# IceBoard-Rev3.net
KiCad netlist of a schematic drawn in EAGLE
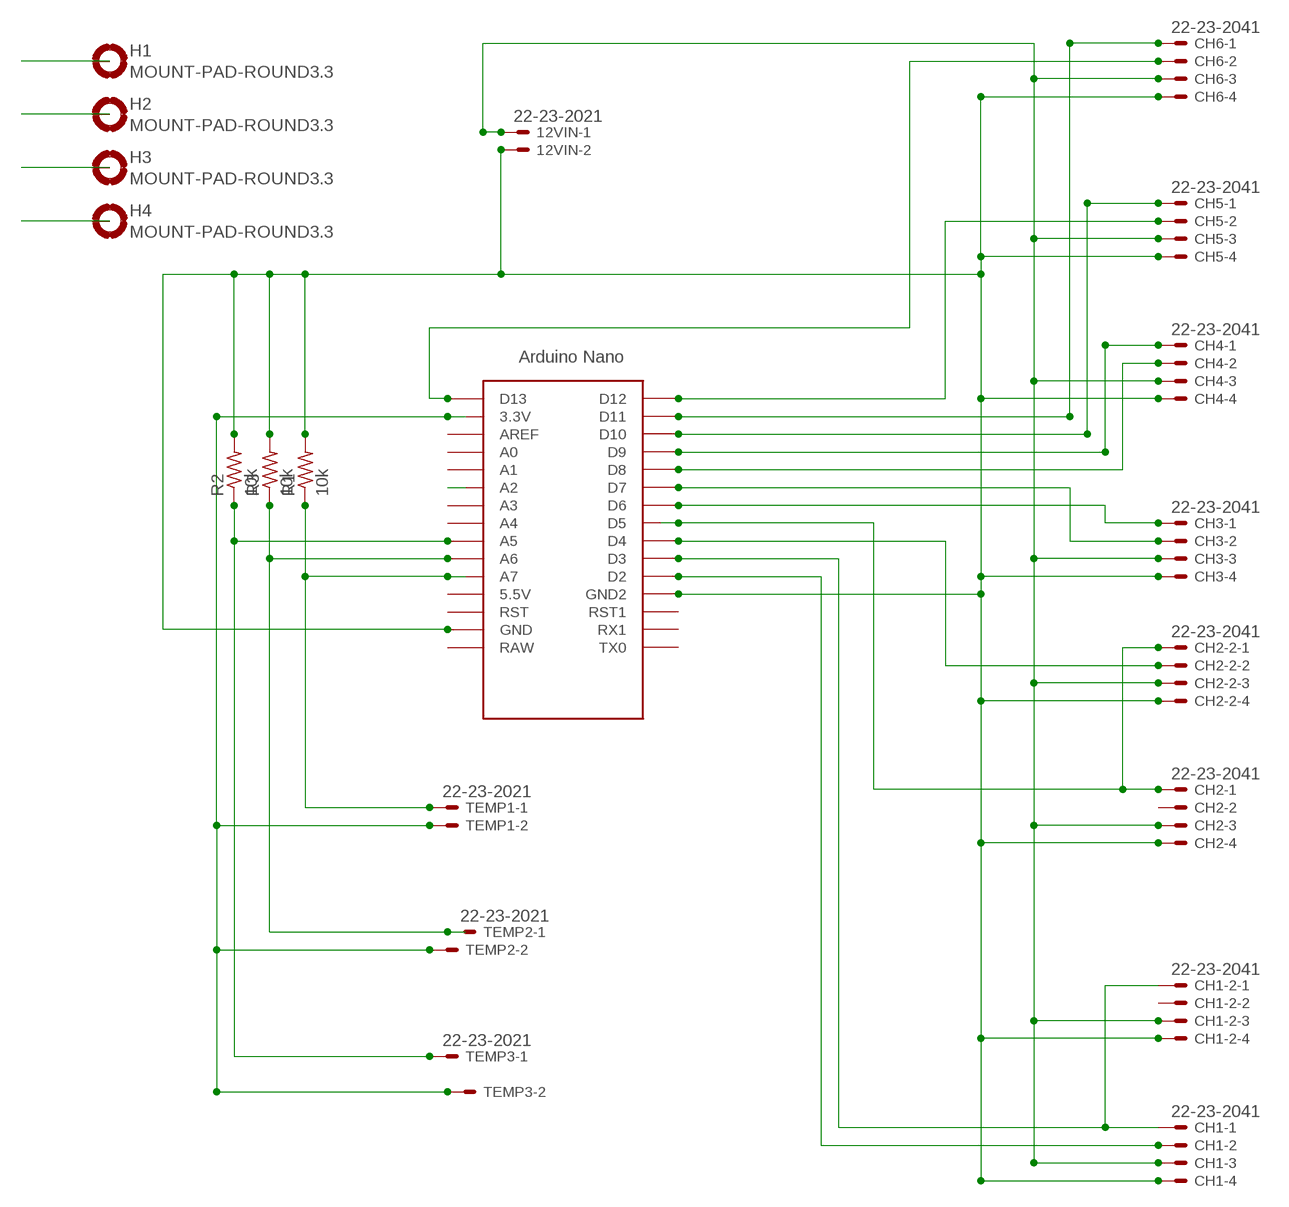
[diagram p0: schematic, sheet 1]

(export (version "E")
  (design (tool "Eeschema 10.0.6"))
  (components
    (comp (ref "12VIN")
      (value "22-23-2021")
      (footprint "eagle-import:22-23-2021")
      (fields (field (name "MF") "MOLEX"))
      (libsource (lib "eagle-import") (part "22-23-2021"))
    )
    (comp (ref "CH1")
      (value "22-23-2041")
      (footprint "eagle-import:22-23-2041")
      (fields (field (name "MF") "MOLEX"))
      (libsource (lib "eagle-import") (part "22-23-2041"))
    )
    (comp (ref "CH1-2")
      (value "22-23-2041")
      (footprint "eagle-import:22-23-2041")
      (fields (field (name "MF") "MOLEX"))
      (libsource (lib "eagle-import") (part "22-23-2041"))
    )
    (comp (ref "CH2")
      (value "22-23-2041")
      (footprint "eagle-import:22-23-2041")
      (fields (field (name "MF") "MOLEX"))
      (libsource (lib "eagle-import") (part "22-23-2041"))
    )
    (comp (ref "CH2-2")
      (value "22-23-2041")
      (footprint "eagle-import:22-23-2041")
      (fields (field (name "MF") "MOLEX"))
      (libsource (lib "eagle-import") (part "22-23-2041"))
    )
    (comp (ref "CH3")
      (value "22-23-2041")
      (footprint "eagle-import:22-23-2041")
      (fields (field (name "MF") "MOLEX"))
      (libsource (lib "eagle-import") (part "22-23-2041"))
    )
    (comp (ref "CH4")
      (value "22-23-2041")
      (footprint "eagle-import:22-23-2041")
      (fields (field (name "MF") "MOLEX"))
      (libsource (lib "eagle-import") (part "22-23-2041"))
    )
    (comp (ref "CH5")
      (value "22-23-2041")
      (footprint "eagle-import:22-23-2041")
      (fields (field (name "MF") "MOLEX"))
      (libsource (lib "eagle-import") (part "22-23-2041"))
    )
    (comp (ref "CH6")
      (value "22-23-2041")
      (footprint "eagle-import:22-23-2041")
      (fields (field (name "MF") "MOLEX"))
      (libsource (lib "eagle-import") (part "22-23-2041"))
    )
    (comp (ref "H1")
      (value "MOUNT-PAD-ROUND3.3")
      (footprint "eagle-import:3,3-PAD")
      (libsource (lib "eagle-import") (part "MOUNT-PAD-ROUND3.3"))
    )
    (comp (ref "H2")
      (value "MOUNT-PAD-ROUND3.3")
      (footprint "eagle-import:3,3-PAD")
      (libsource (lib "eagle-import") (part "MOUNT-PAD-ROUND3.3"))
    )
    (comp (ref "H3")
      (value "MOUNT-PAD-ROUND3.3")
      (footprint "eagle-import:3,3-PAD")
      (libsource (lib "eagle-import") (part "MOUNT-PAD-ROUND3.3"))
    )
    (comp (ref "H4")
      (value "MOUNT-PAD-ROUND3.3")
      (footprint "eagle-import:3,3-PAD")
      (libsource (lib "eagle-import") (part "MOUNT-PAD-ROUND3.3"))
    )
    (comp (ref "R1")
      (value "10k")
      (footprint "eagle-import:R0805")
      (libsource (lib "eagle-import") (part "R-US_R0805"))
    )
    (comp (ref "R2")
      (value "10k")
      (footprint "eagle-import:R0805")
      (libsource (lib "eagle-import") (part "R-US_R0805"))
    )
    (comp (ref "R3")
      (value "10k")
      (footprint "eagle-import:R0805")
      (libsource (lib "eagle-import") (part "R-US_R0805"))
    )
    (comp (ref "TEMP1")
      (value "22-23-2021")
      (footprint "eagle-import:22-23-2021")
      (fields (field (name "MF") "MOLEX"))
      (libsource (lib "eagle-import") (part "22-23-2021"))
    )
    (comp (ref "TEMP2")
      (value "22-23-2021")
      (footprint "eagle-import:22-23-2021")
      (fields (field (name "MF") "MOLEX"))
      (libsource (lib "eagle-import") (part "22-23-2021"))
    )
    (comp (ref "TEMP3")
      (value "22-23-2021")
      (footprint "eagle-import:22-23-2021")
      (fields (field (name "MF") "MOLEX"))
      (libsource (lib "eagle-import") (part "22-23-2021"))
    )
    (comp (ref "U$1")
      (value "NANO")
      (footprint "eagle-import:NANO")
      (libsource (lib "eagle-import") (part "NANO"))
    )
  )
  (nets
    (net (code "1") (name "/GND") (class "Default")
      (node (ref "12VIN") (pin "2") (pinfunction "S_2") (pintype "passive"))
      (node (ref "CH1") (pin "4") (pinfunction "S_4") (pintype "passive"))
      (node (ref "CH1-2") (pin "4") (pinfunction "S_4") (pintype "passive"))
      (node (ref "CH2") (pin "4") (pinfunction "S_4") (pintype "passive"))
      (node (ref "CH2-2") (pin "4") (pinfunction "S_4") (pintype "passive"))
      (node (ref "CH3") (pin "4") (pinfunction "S_4") (pintype "passive"))
      (node (ref "CH4") (pin "4") (pinfunction "S_4") (pintype "passive"))
      (node (ref "CH5") (pin "4") (pinfunction "S_4") (pintype "passive"))
      (node (ref "CH6") (pin "4") (pinfunction "S_4") (pintype "passive"))
      (node (ref "R1") (pin "2") (pinfunction "2_2") (pintype "passive"))
      (node (ref "R2") (pin "2") (pinfunction "2_2") (pintype "passive"))
      (node (ref "R3") (pin "2") (pinfunction "2_2") (pintype "passive"))
      (node (ref "U$1") (pin "GND") (pinfunction "GND_GND") (pintype "bidirectional"))
      (node (ref "U$1") (pin "GND1") (pinfunction "GND2_GND1") (pintype "bidirectional"))
    )
    (net (code "2") (name "Net-(12VINA-S)") (class "Default")
      (node (ref "12VIN") (pin "1") (pinfunction "S_1") (pintype "passive"))
      (node (ref "CH1") (pin "3") (pinfunction "S_3") (pintype "passive"))
      (node (ref "CH1-2") (pin "3") (pinfunction "S_3") (pintype "passive"))
      (node (ref "CH2") (pin "3") (pinfunction "S_3") (pintype "passive"))
      (node (ref "CH2-2") (pin "3") (pinfunction "S_3") (pintype "passive"))
      (node (ref "CH3") (pin "3") (pinfunction "S_3") (pintype "passive"))
      (node (ref "CH4") (pin "3") (pinfunction "S_3") (pintype "passive"))
      (node (ref "CH5") (pin "3") (pinfunction "S_3") (pintype "passive"))
      (node (ref "CH6") (pin "3") (pinfunction "S_3") (pintype "passive"))
    )
    (net (code "3") (name "Net-(CH1-2A-S)") (class "Default")
      (node (ref "CH1") (pin "1") (pinfunction "S_1") (pintype "passive"))
      (node (ref "CH1-2") (pin "1") (pinfunction "S_1") (pintype "passive"))
      (node (ref "U$1") (pin "D3") (pinfunction "D3_D3") (pintype "bidirectional"))
    )
    (net (code "4") (name "Net-(CH1B-S)") (class "Default")
      (node (ref "CH1") (pin "2") (pinfunction "S_2") (pintype "passive"))
      (node (ref "U$1") (pin "D2") (pinfunction "D2_D2") (pintype "bidirectional"))
    )
    (net (code "5") (name "Net-(CH2-2A-S)") (class "Default")
      (node (ref "CH2") (pin "1") (pinfunction "S_1") (pintype "passive"))
      (node (ref "CH2-2") (pin "1") (pinfunction "S_1") (pintype "passive"))
      (node (ref "U$1") (pin "D5") (pinfunction "D5_D5") (pintype "bidirectional"))
    )
    (net (code "6") (name "Net-(CH2-2B-S)") (class "Default")
      (node (ref "CH2-2") (pin "2") (pinfunction "S_2") (pintype "passive"))
      (node (ref "U$1") (pin "D4") (pinfunction "D4_D4") (pintype "bidirectional"))
    )
    (net (code "7") (name "Net-(CH3A-S)") (class "Default")
      (node (ref "CH3") (pin "1") (pinfunction "S_1") (pintype "passive"))
      (node (ref "U$1") (pin "D6") (pinfunction "D6_D6") (pintype "bidirectional"))
    )
    (net (code "8") (name "Net-(CH3B-S)") (class "Default")
      (node (ref "CH3") (pin "2") (pinfunction "S_2") (pintype "passive"))
      (node (ref "U$1") (pin "D7") (pinfunction "D7_D7") (pintype "bidirectional"))
    )
    (net (code "9") (name "Net-(CH4A-S)") (class "Default")
      (node (ref "CH4") (pin "1") (pinfunction "S_1") (pintype "passive"))
      (node (ref "U$1") (pin "D9") (pinfunction "D9_D9") (pintype "bidirectional"))
    )
    (net (code "10") (name "Net-(CH4B-S)") (class "Default")
      (node (ref "CH4") (pin "2") (pinfunction "S_2") (pintype "passive"))
      (node (ref "U$1") (pin "D8") (pinfunction "D8_D8") (pintype "bidirectional"))
    )
    (net (code "11") (name "Net-(CH5A-S)") (class "Default")
      (node (ref "CH5") (pin "1") (pinfunction "S_1") (pintype "passive"))
      (node (ref "U$1") (pin "D10") (pinfunction "D10_D10") (pintype "bidirectional"))
    )
    (net (code "12") (name "Net-(CH5B-S)") (class "Default")
      (node (ref "CH5") (pin "2") (pinfunction "S_2") (pintype "passive"))
      (node (ref "U$1") (pin "D12") (pinfunction "D12_D12") (pintype "bidirectional"))
    )
    (net (code "13") (name "Net-(CH6A-S)") (class "Default")
      (node (ref "CH6") (pin "1") (pinfunction "S_1") (pintype "passive"))
      (node (ref "U$1") (pin "D11") (pinfunction "D11_D11") (pintype "bidirectional"))
    )
    (net (code "14") (name "Net-(CH6B-S)") (class "Default")
      (node (ref "CH6") (pin "2") (pinfunction "S_2") (pintype "passive"))
      (node (ref "U$1") (pin "D13") (pinfunction "D13_D13") (pintype "bidirectional"))
    )
    (net (code "15") (name "Net-(TEMP1A-S)") (class "Default")
      (node (ref "R1") (pin "1") (pinfunction "1_1") (pintype "passive"))
      (node (ref "TEMP1") (pin "1") (pinfunction "S_1") (pintype "passive"))
      (node (ref "U$1") (pin "A7") (pinfunction "A7_A7") (pintype "bidirectional"))
    )
    (net (code "16") (name "Net-(TEMP1B-S)") (class "Default")
      (node (ref "TEMP1") (pin "2") (pinfunction "S_2") (pintype "passive"))
      (node (ref "TEMP2") (pin "2") (pinfunction "S_2") (pintype "passive"))
      (node (ref "TEMP3") (pin "2") (pinfunction "S_2") (pintype "passive"))
      (node (ref "U$1") (pin "3.3V") (pinfunction "3.3V_3.3V") (pintype "bidirectional"))
    )
    (net (code "17") (name "Net-(TEMP2A-S)") (class "Default")
      (node (ref "R3") (pin "1") (pinfunction "1_1") (pintype "passive"))
      (node (ref "TEMP2") (pin "1") (pinfunction "S_1") (pintype "passive"))
      (node (ref "U$1") (pin "A6") (pinfunction "A6_A6") (pintype "bidirectional"))
    )
    (net (code "18") (name "Net-(TEMP3A-S)") (class "Default")
      (node (ref "R2") (pin "1") (pinfunction "1_1") (pintype "passive"))
      (node (ref "TEMP3") (pin "1") (pinfunction "S_1") (pintype "passive"))
      (node (ref "U$1") (pin "A5") (pinfunction "A5_A5") (pintype "bidirectional"))
    )
    (net (code "19") (name "unconnected-(CH1-2B-S-Pad2)") (class "Default")
      (node (ref "CH1-2") (pin "2") (pinfunction "S_2") (pintype "passive"))
    )
    (net (code "20") (name "unconnected-(CH2B-S-Pad2)") (class "Default")
      (node (ref "CH2") (pin "2") (pinfunction "S_2") (pintype "passive"))
    )
    (net (code "21") (name "unconnected-(H1-MOUNT-PadB3,3)") (class "Default")
      (node (ref "H1") (pin "B3,3") (pinfunction "MOUNT_B3,3") (pintype "passive"))
    )
    (net (code "22") (name "unconnected-(H2-MOUNT-PadB3,3)") (class "Default")
      (node (ref "H2") (pin "B3,3") (pinfunction "MOUNT_B3,3") (pintype "passive"))
    )
    (net (code "23") (name "unconnected-(H3-MOUNT-PadB3,3)") (class "Default")
      (node (ref "H3") (pin "B3,3") (pinfunction "MOUNT_B3,3") (pintype "passive"))
    )
    (net (code "24") (name "unconnected-(H4-MOUNT-PadB3,3)") (class "Default")
      (node (ref "H4") (pin "B3,3") (pinfunction "MOUNT_B3,3") (pintype "passive"))
    )
    (net (code "25") (name "unconnected-(U$1-5.5V-Pad5V)") (class "Default")
      (node (ref "U$1") (pin "5V") (pinfunction "5.5V_5V") (pintype "bidirectional"))
    )
    (net (code "26") (name "unconnected-(U$1-PadA0)") (class "Default")
      (node (ref "U$1") (pin "A0") (pinfunction "A0_A0") (pintype "bidirectional"))
    )
    (net (code "27") (name "unconnected-(U$1-PadA1)") (class "Default")
      (node (ref "U$1") (pin "A1") (pinfunction "A1_A1") (pintype "bidirectional"))
    )
    (net (code "28") (name "unconnected-(U$1-PadA2)") (class "Default")
      (node (ref "U$1") (pin "A2") (pinfunction "A2_A2") (pintype "bidirectional"))
    )
    (net (code "29") (name "unconnected-(U$1-PadA3)") (class "Default")
      (node (ref "U$1") (pin "A3") (pinfunction "A3_A3") (pintype "bidirectional"))
    )
    (net (code "30") (name "unconnected-(U$1-PadA4)") (class "Default")
      (node (ref "U$1") (pin "A4") (pinfunction "A4_A4") (pintype "bidirectional"))
    )
    (net (code "31") (name "unconnected-(U$1-PadAREF)") (class "Default")
      (node (ref "U$1") (pin "AREF") (pinfunction "AREF_AREF") (pintype "bidirectional"))
    )
    (net (code "32") (name "unconnected-(U$1-PadICSP1)") (class "Default")
      (node (ref "U$1") (pin "ICSP1") (pinfunction "ICSP1_ICSP1") (pintype "bidirectional"))
    )
    (net (code "33") (name "unconnected-(U$1-PadICSP2)") (class "Default")
      (node (ref "U$1") (pin "ICSP2") (pinfunction "ICSP2_ICSP2") (pintype "bidirectional"))
    )
    (net (code "34") (name "unconnected-(U$1-PadICSP3)") (class "Default")
      (node (ref "U$1") (pin "ICSP3") (pinfunction "ICSP3_ICSP3") (pintype "bidirectional"))
    )
    (net (code "35") (name "unconnected-(U$1-PadICSP4)") (class "Default")
      (node (ref "U$1") (pin "ICSP4") (pinfunction "ICSP4_ICSP4") (pintype "bidirectional"))
    )
    (net (code "36") (name "unconnected-(U$1-PadICSP5)") (class "Default")
      (node (ref "U$1") (pin "ICSP5") (pinfunction "ICSP5_ICSP5") (pintype "bidirectional"))
    )
    (net (code "37") (name "unconnected-(U$1-PadICSP6)") (class "Default")
      (node (ref "U$1") (pin "ICSP6") (pinfunction "ICSP6_ICSP6") (pintype "bidirectional"))
    )
    (net (code "38") (name "unconnected-(U$1-PadRAW)") (class "Default")
      (node (ref "U$1") (pin "RAW") (pinfunction "RAW_RAW") (pintype "bidirectional"))
    )
    (net (code "39") (name "unconnected-(U$1-PadRST)") (class "Default")
      (node (ref "U$1") (pin "RST") (pinfunction "RST_RST") (pintype "bidirectional"))
    )
    (net (code "40") (name "unconnected-(U$1-PadRST1)") (class "Default")
      (node (ref "U$1") (pin "RST1") (pinfunction "RST1_RST1") (pintype "bidirectional"))
    )
    (net (code "41") (name "unconnected-(U$1-PadRX1)") (class "Default")
      (node (ref "U$1") (pin "RX1") (pinfunction "RX1_RX1") (pintype "bidirectional"))
    )
    (net (code "42") (name "unconnected-(U$1-PadTX0)") (class "Default")
      (node (ref "U$1") (pin "TX0") (pinfunction "TX0_TX0") (pintype "bidirectional"))
    )
  )
)
